# kick.net
KiCad netlist of a schematic drawn in EAGLE
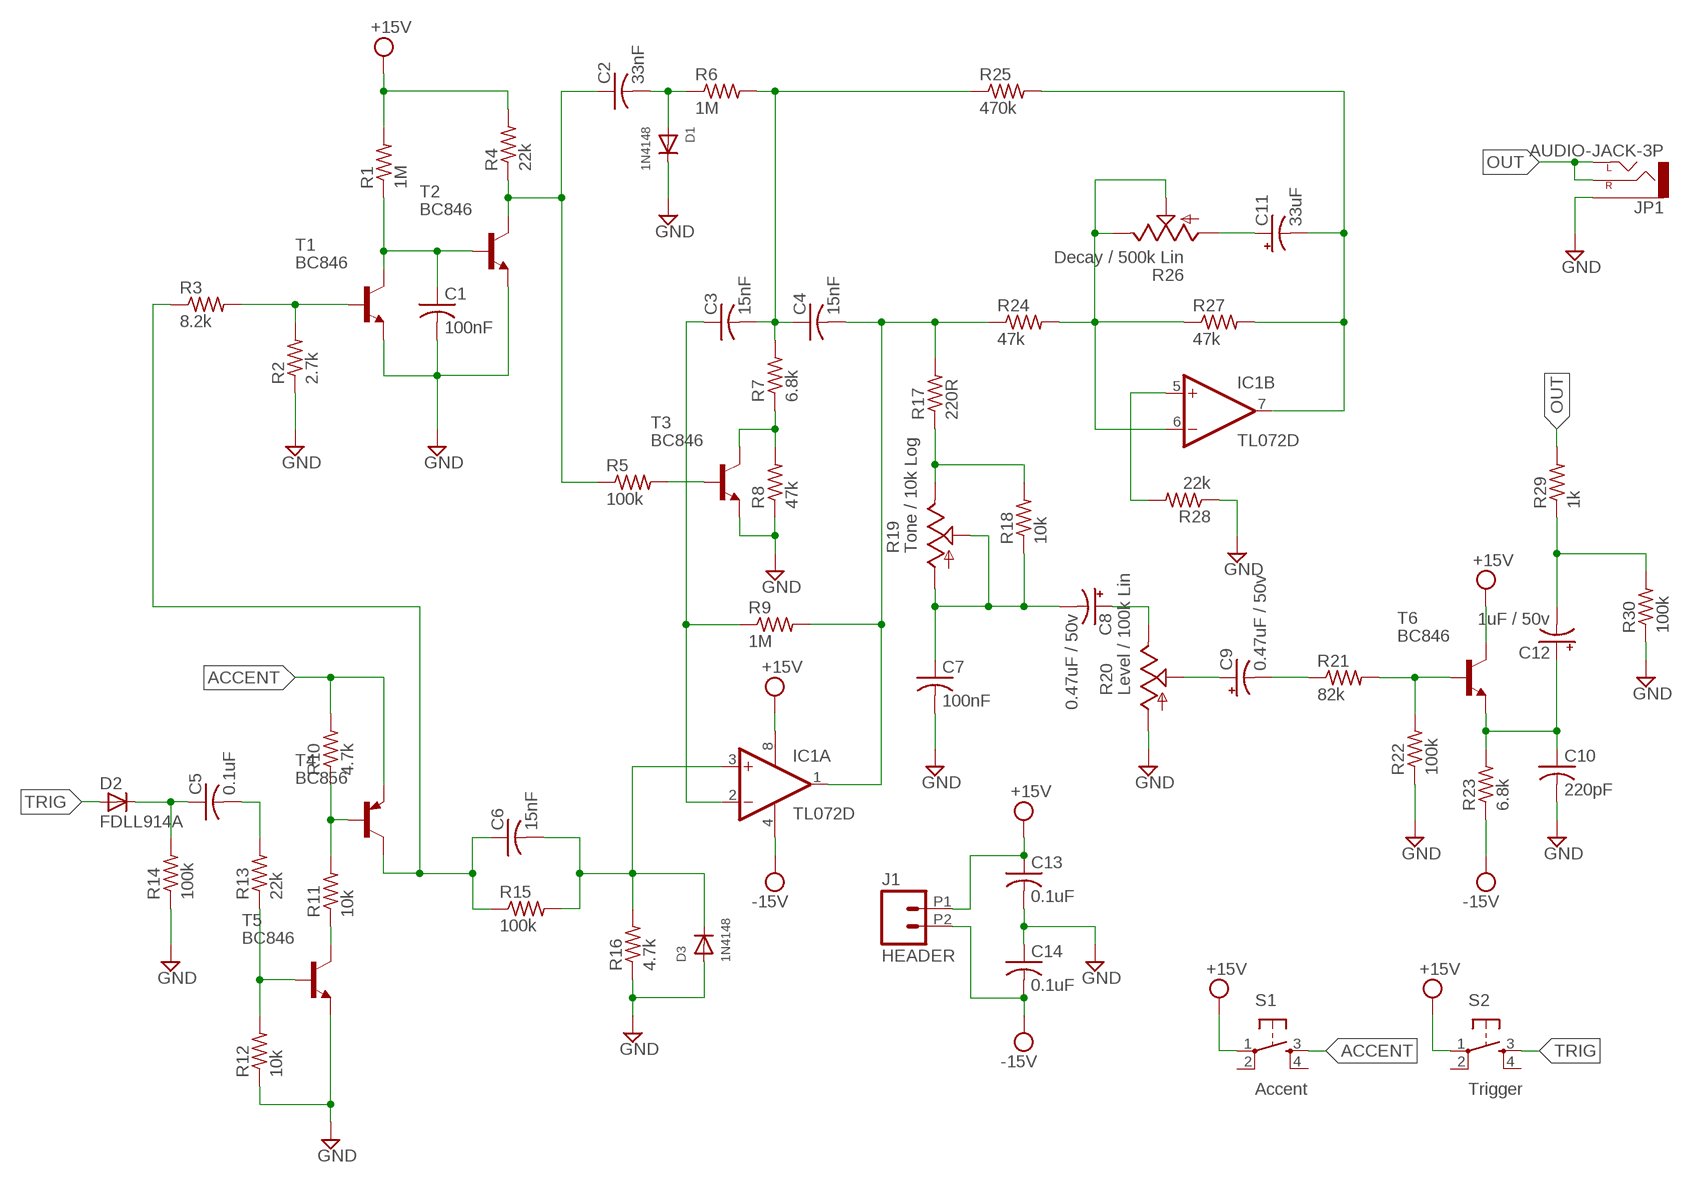
[diagram p0: schematic, sheet 1]

(export (version "E")
  (design (tool "Eeschema 10.0.6"))
  (components
    (comp (ref "C1")
      (value "100nF")
      (footprint "eagle-import:C0805")
      (fields (field (name "PARTNO") "C0805C104K5RACTU"))
      (libsource (lib "eagle-import") (part "C-USC0805"))
    )
    (comp (ref "C2")
      (value "33nF")
      (footprint "eagle-import:C0805")
      (fields (field (name "PARTNO") "CL21B333KBANNNC"))
      (libsource (lib "eagle-import") (part "C-USC0805"))
    )
    (comp (ref "C3")
      (value "15nF")
      (footprint "eagle-import:C0805")
      (fields (field (name "PARTNO") "CC0805KRX7R9BB153"))
      (libsource (lib "eagle-import") (part "C-USC0805"))
    )
    (comp (ref "C4")
      (value "15nF")
      (footprint "eagle-import:C0805")
      (fields (field (name "PARTNO") "CC0805KRX7R9BB153"))
      (libsource (lib "eagle-import") (part "C-USC0805"))
    )
    (comp (ref "C5")
      (value "0.1uF")
      (footprint "eagle-import:C0805")
      (fields (field (name "PARTNO") "C0805C104K5RACTU"))
      (libsource (lib "eagle-import") (part "C-USC0805"))
    )
    (comp (ref "C6")
      (value "15nF")
      (footprint "eagle-import:C0805")
      (fields (field (name "PARTNO") "CC0805KRX7R9BB153"))
      (libsource (lib "eagle-import") (part "C-USC0805"))
    )
    (comp (ref "C7")
      (value "100nF")
      (footprint "eagle-import:C0805")
      (fields (field (name "PARTNO") "C0805C104K5RACTU"))
      (libsource (lib "eagle-import") (part "C-USC0805"))
    )
    (comp (ref "C8")
      (value "0.47uF / 50v")
      (footprint "eagle-import:PANASONIC_VS_B-2")
      (fields (field (name "PARTNO") "EEE-1HAR47AR"))
      (libsource (lib "eagle-import") (part "CAP-POLPANASONIC_B-2"))
    )
    (comp (ref "C9")
      (value "0.47uF / 50v")
      (footprint "eagle-import:PANASONIC_VS_B-2")
      (fields (field (name "PARTNO") "EEE-1HAR47AR"))
      (libsource (lib "eagle-import") (part "CAP-POLPANASONIC_B-2"))
    )
    (comp (ref "C10")
      (value "220pF")
      (footprint "eagle-import:C0805")
      (fields (field (name "PARTNO") "CC0805KRX7R9BB221"))
      (libsource (lib "eagle-import") (part "C-USC0805"))
    )
    (comp (ref "C11")
      (value "33uF")
      (footprint "eagle-import:PANASONIC_VS_B-2")
      (fields (field (name "PARTNO") "EEE-1AA330WAR"))
      (libsource (lib "eagle-import") (part "CAP-POLPANASONIC_B-2"))
    )
    (comp (ref "C12")
      (value "1uF / 50v")
      (footprint "eagle-import:PANASONIC_VS_B-2")
      (fields (field (name "PARTNO") "EEE-1HA010SR"))
      (libsource (lib "eagle-import") (part "CAP-POLPANASONIC_B-2"))
    )
    (comp (ref "C13")
      (value "0.1uF")
      (footprint "eagle-import:C0805")
      (fields (field (name "PARTNO") "C0805C104K5RACTU"))
      (libsource (lib "eagle-import") (part "C-USC0805"))
    )
    (comp (ref "C14")
      (value "0.1uF")
      (footprint "eagle-import:C0805")
      (fields (field (name "PARTNO") "C0805C104K5RACTU"))
      (libsource (lib "eagle-import") (part "C-USC0805"))
    )
    (comp (ref "D1")
      (value "1N4148")
      (footprint "eagle-import:SOD-323F")
      (fields (field (name "PARTNO") "1N4148WS"))
      (libsource (lib "eagle-import") (part "DIODESOD-323F"))
    )
    (comp (ref "D2")
      (value "FDLL914A")
      (footprint "eagle-import:MELF-MLL34")
      (libsource (lib "eagle-import") (part "D-MLL-34"))
    )
    (comp (ref "D3")
      (value "1N4148")
      (footprint "eagle-import:SOD-323F")
      (fields (field (name "PARTNO") "1N4148WS"))
      (libsource (lib "eagle-import") (part "DIODESOD-323F"))
    )
    (comp (ref "IC1")
      (value "TL072D")
      (footprint "eagle-import:SO08")
      (fields (field (name "PARTNO") "TL072SG-13"))
      (libsource (lib "eagle-import") (part "TL072D"))
    )
    (comp (ref "J1")
      (value "HEADER")
      (footprint "eagle-import:1X02-5.08-SCREWTERM")
      (libsource (lib "eagle-import") (part "HEADER"))
    )
    (comp (ref "JP1")
      (value "AUDIO-JACK-3P")
      (footprint "eagle-import:CUI-352X-SMT")
      (fields (field (name "PARTNO") "SJ-3523-SMT-TR"))
      (libsource (lib "eagle-import") (part "AUDIO-JACK-3P"))
    )
    (comp (ref "R1")
      (value "1M")
      (footprint "eagle-import:R0805")
      (fields (field (name "PARTNO") "RMCF0805FT1M00"))
      (libsource (lib "eagle-import") (part "R-US_R0805"))
    )
    (comp (ref "R2")
      (value "2.7k")
      (footprint "eagle-import:R0805")
      (fields (field (name "PARTNO") "RMCF0805FT2K70"))
      (libsource (lib "eagle-import") (part "R-US_R0805"))
    )
    (comp (ref "R3")
      (value "8.2k")
      (footprint "eagle-import:R0805")
      (fields (field (name "PARTNO") "RMCF0805FT8K20"))
      (libsource (lib "eagle-import") (part "R-US_R0805"))
    )
    (comp (ref "R4")
      (value "22k")
      (footprint "eagle-import:R0805")
      (fields (field (name "PARTNO") "RMCF0805FT22K0"))
      (libsource (lib "eagle-import") (part "R-US_R0805"))
    )
    (comp (ref "R5")
      (value "100k")
      (footprint "eagle-import:R0805")
      (fields (field (name "PARTNO") "RMCF0805FT100K"))
      (libsource (lib "eagle-import") (part "R-US_R0805"))
    )
    (comp (ref "R6")
      (value "1M")
      (footprint "eagle-import:R0805")
      (fields (field (name "PARTNO") "RMCF0805FT1M00"))
      (libsource (lib "eagle-import") (part "R-US_R0805"))
    )
    (comp (ref "R7")
      (value "6.8k")
      (footprint "eagle-import:R0805")
      (fields (field (name "PARTNO") "MCR10ERTF6801"))
      (libsource (lib "eagle-import") (part "R-US_R0805"))
    )
    (comp (ref "R8")
      (value "47k")
      (footprint "eagle-import:R0805")
      (fields (field (name "PARTNO") "RMCF0805FT47K0"))
      (libsource (lib "eagle-import") (part "R-US_R0805"))
    )
    (comp (ref "R9")
      (value "1M")
      (footprint "eagle-import:R0805")
      (fields (field (name "PARTNO") "RMCF0805FT1M00"))
      (libsource (lib "eagle-import") (part "R-US_R0805"))
    )
    (comp (ref "R10")
      (value "4.7k")
      (footprint "eagle-import:R0805")
      (fields (field (name "PARTNO") "RMCF0805FT4K70"))
      (libsource (lib "eagle-import") (part "R-US_R0805"))
    )
    (comp (ref "R11")
      (value "10k")
      (footprint "eagle-import:R0805")
      (fields (field (name "PARTNO") "RMCF0805FT10K0"))
      (libsource (lib "eagle-import") (part "R-US_R0805"))
    )
    (comp (ref "R12")
      (value "10k")
      (footprint "eagle-import:R0805")
      (fields (field (name "PARTNO") "RMCF0805FT10K0"))
      (libsource (lib "eagle-import") (part "R-US_R0805"))
    )
    (comp (ref "R13")
      (value "22k")
      (footprint "eagle-import:R0805")
      (fields (field (name "PARTNO") "RMCF0805FT22K0"))
      (libsource (lib "eagle-import") (part "R-US_R0805"))
    )
    (comp (ref "R14")
      (value "100k")
      (footprint "eagle-import:R0805")
      (fields (field (name "PARTNO") "RMCF0805FT100K"))
      (libsource (lib "eagle-import") (part "R-US_R0805"))
    )
    (comp (ref "R15")
      (value "100k")
      (footprint "eagle-import:R0805")
      (fields (field (name "PARTNO") "RMCF0805FT100K"))
      (libsource (lib "eagle-import") (part "R-US_R0805"))
    )
    (comp (ref "R16")
      (value "4.7k")
      (footprint "eagle-import:R0805")
      (fields (field (name "PARTNO") "RMCF0805FT4K70"))
      (libsource (lib "eagle-import") (part "R-US_R0805"))
    )
    (comp (ref "R17")
      (value "220R")
      (footprint "eagle-import:R0805")
      (fields (field (name "PARTNO") "RMCF0805FT220R"))
      (libsource (lib "eagle-import") (part "R-US_R0805"))
    )
    (comp (ref "R18")
      (value "10k")
      (footprint "eagle-import:R0805")
      (fields (field (name "PARTNO") "RMCF0805FT10K0"))
      (libsource (lib "eagle-import") (part "R-US_R0805"))
    )
    (comp (ref "R19")
      (value "Tone / 10k Log")
      (footprint "eagle-import:POTENTIOMETER-PTV09")
      (fields (field (name "PARTNO") "PTV09A-4020F-A103"))
      (libsource (lib "eagle-import") (part "POTPTV09-H"))
    )
    (comp (ref "R20")
      (value "Level / 100k Lin")
      (footprint "eagle-import:POTENTIOMETER-CTS296")
      (fields (field (name "PARTNO") "296UD104B1N"))
      (libsource (lib "eagle-import") (part "POTCTS296"))
    )
    (comp (ref "R21")
      (value "82k")
      (footprint "eagle-import:R0805")
      (fields (field (name "PARTNO") "RMCF0805FT82K0"))
      (libsource (lib "eagle-import") (part "R-US_R0805"))
    )
    (comp (ref "R22")
      (value "100k")
      (footprint "eagle-import:R0805")
      (fields (field (name "PARTNO") "RMCF0805FT100K"))
      (libsource (lib "eagle-import") (part "R-US_R0805"))
    )
    (comp (ref "R23")
      (value "6.8k")
      (footprint "eagle-import:R0805")
      (fields (field (name "PARTNO") "MCR10ERTF6801"))
      (libsource (lib "eagle-import") (part "R-US_R0805"))
    )
    (comp (ref "R24")
      (value "47k")
      (footprint "eagle-import:R0805")
      (fields (field (name "PARTNO") "RMCF0805FT47K0"))
      (libsource (lib "eagle-import") (part "R-US_R0805"))
    )
    (comp (ref "R25")
      (value "470k")
      (footprint "eagle-import:R0805")
      (fields (field (name "PARTNO") "CRCW0805470KFKEA"))
      (libsource (lib "eagle-import") (part "R-US_R0805"))
    )
    (comp (ref "R26")
      (value "Decay / 500k Lin")
      (footprint "eagle-import:POTENTIOMETER-PTV09")
      (fields (field (name "PARTNO") "296UD504B1N"))
      (libsource (lib "eagle-import") (part "POTPTV09-H"))
    )
    (comp (ref "R27")
      (value "47k")
      (footprint "eagle-import:R0805")
      (fields (field (name "PARTNO") "RMCF0805FT47K0"))
      (libsource (lib "eagle-import") (part "R-US_R0805"))
    )
    (comp (ref "R28")
      (value "22k")
      (footprint "eagle-import:R0805")
      (fields (field (name "PARTNO") "RMCF0805FT22K0"))
      (libsource (lib "eagle-import") (part "R-US_R0805"))
    )
    (comp (ref "R29")
      (value "1k")
      (footprint "eagle-import:R0805")
      (fields (field (name "PARTNO") "RMCF0805FT1K00"))
      (libsource (lib "eagle-import") (part "R-US_R0805"))
    )
    (comp (ref "R30")
      (value "100k")
      (footprint "eagle-import:R0805")
      (fields (field (name "PARTNO") "RMCF0805FT100K"))
      (libsource (lib "eagle-import") (part "R-US_R0805"))
    )
    (comp (ref "S1")
      (value "Accent")
      (footprint "eagle-import:TACTILE-SWITCH-SMD")
      (fields (field (name "PARTNO") "PTS525SM10SMTR LFS"))
      (libsource (lib "eagle-import") (part "TAC_SWITCHSMD"))
    )
    (comp (ref "S2")
      (value "Trigger")
      (footprint "eagle-import:TACTILE-SWITCH-SMD")
      (fields (field (name "PARTNO") "PTS525SM10SMTR LFS"))
      (libsource (lib "eagle-import") (part "TAC_SWITCHSMD"))
    )
    (comp (ref "T1")
      (value "BC846")
      (footprint "eagle-import:SOT23")
      (fields (field (name "PARTNO") "BC846BMTF"))
      (libsource (lib "eagle-import") (part "BC846"))
    )
    (comp (ref "T2")
      (value "BC846")
      (footprint "eagle-import:SOT23")
      (fields (field (name "PARTNO") "BC846BMTF"))
      (libsource (lib "eagle-import") (part "BC846"))
    )
    (comp (ref "T3")
      (value "BC846")
      (footprint "eagle-import:SOT23")
      (fields (field (name "PARTNO") "BC846BMTF"))
      (libsource (lib "eagle-import") (part "BC846"))
    )
    (comp (ref "T4")
      (value "BC856")
      (footprint "eagle-import:SOT23-BEC")
      (fields (field (name "PARTNO") "BC856BMTF"))
      (libsource (lib "eagle-import") (part "-PNP-SOT23-BECBC856B"))
    )
    (comp (ref "T5")
      (value "BC846")
      (footprint "eagle-import:SOT23")
      (fields (field (name "PARTNO") "BC846BMTF"))
      (libsource (lib "eagle-import") (part "BC846"))
    )
    (comp (ref "T6")
      (value "BC846")
      (footprint "eagle-import:SOT23")
      (fields (field (name "PARTNO") "BC846BMTF"))
      (libsource (lib "eagle-import") (part "BC846"))
    )
  )
  (nets
    (net (code "1") (name "+15V") (class "Default")
      (node (ref "C13") (pin "1") (pinfunction "1_1") (pintype "passive"))
      (node (ref "IC1") (pin "8") (pinfunction "V+_8") (pintype "power_in"))
      (node (ref "J1") (pin "P1") (pinfunction "2_P1") (pintype "passive"))
      (node (ref "R1") (pin "2") (pinfunction "2_2") (pintype "passive"))
      (node (ref "R4") (pin "2") (pinfunction "2_2") (pintype "passive"))
      (node (ref "S1") (pin "1") (pinfunction "1_1") (pintype "passive"))
      (node (ref "S2") (pin "1") (pinfunction "1_1") (pintype "passive"))
      (node (ref "T6") (pin "3") (pinfunction "C_3") (pintype "passive"))
    )
    (net (code "2") (name "-15V") (class "Default")
      (node (ref "C14") (pin "2") (pinfunction "2_2") (pintype "passive"))
      (node (ref "IC1") (pin "4") (pinfunction "V-_4") (pintype "power_in"))
      (node (ref "J1") (pin "P2") (pinfunction "1_P2") (pintype "passive"))
      (node (ref "R23") (pin "1") (pinfunction "1_1") (pintype "passive"))
    )
    (net (code "3") (name "ACCENT") (class "Default")
      (node (ref "R10") (pin "2") (pinfunction "2_2") (pintype "passive"))
      (node (ref "S1") (pin "3") (pinfunction "3_3") (pintype "passive"))
      (node (ref "T4") (pin "E") (pinfunction "E_E") (pintype "passive"))
    )
    (net (code "4") (name "GND") (class "Default")
      (node (ref "C1") (pin "2") (pinfunction "2_2") (pintype "passive"))
      (node (ref "C10") (pin "2") (pinfunction "2_2") (pintype "passive"))
      (node (ref "C13") (pin "2") (pinfunction "2_2") (pintype "passive"))
      (node (ref "C14") (pin "1") (pinfunction "1_1") (pintype "passive"))
      (node (ref "C7") (pin "2") (pinfunction "2_2") (pintype "passive"))
      (node (ref "D1") (pin "C") (pinfunction "C_C") (pintype "passive"))
      (node (ref "D3") (pin "A") (pinfunction "A_A") (pintype "passive"))
      (node (ref "JP1") (pin "1") (pinfunction "SLEEVE_1") (pintype "bidirectional"))
      (node (ref "R12") (pin "1") (pinfunction "1_1") (pintype "passive"))
      (node (ref "R14") (pin "1") (pinfunction "1_1") (pintype "passive"))
      (node (ref "R16") (pin "1") (pinfunction "1_1") (pintype "passive"))
      (node (ref "R2") (pin "1") (pinfunction "1_1") (pintype "passive"))
      (node (ref "R20") (pin "P$1") (pinfunction "A_P$1") (pintype "passive"))
      (node (ref "R22") (pin "1") (pinfunction "1_1") (pintype "passive"))
      (node (ref "R28") (pin "1") (pinfunction "1_1") (pintype "passive"))
      (node (ref "R30") (pin "1") (pinfunction "1_1") (pintype "passive"))
      (node (ref "R8") (pin "1") (pinfunction "1_1") (pintype "passive"))
      (node (ref "T1") (pin "2") (pinfunction "E_2") (pintype "passive"))
      (node (ref "T2") (pin "2") (pinfunction "E_2") (pintype "passive"))
      (node (ref "T3") (pin "2") (pinfunction "E_2") (pintype "passive"))
      (node (ref "T5") (pin "2") (pinfunction "E_2") (pintype "passive"))
    )
    (net (code "5") (name "Net-(C2-Pad2)") (class "Default")
      (node (ref "C2") (pin "2") (pinfunction "2_2") (pintype "passive"))
      (node (ref "D1") (pin "A") (pinfunction "A_A") (pintype "passive"))
      (node (ref "R6") (pin "1") (pinfunction "1_1") (pintype "passive"))
    )
    (net (code "6") (name "Net-(C3-Pad2)") (class "Default")
      (node (ref "C3") (pin "2") (pinfunction "2_2") (pintype "passive"))
      (node (ref "C4") (pin "1") (pinfunction "1_1") (pintype "passive"))
      (node (ref "R25") (pin "1") (pinfunction "1_1") (pintype "passive"))
      (node (ref "R6") (pin "2") (pinfunction "2_2") (pintype "passive"))
      (node (ref "R7") (pin "2") (pinfunction "2_2") (pintype "passive"))
    )
    (net (code "7") (name "Net-(C5-Pad2)") (class "Default")
      (node (ref "C5") (pin "2") (pinfunction "2_2") (pintype "passive"))
      (node (ref "R13") (pin "2") (pinfunction "2_2") (pintype "passive"))
    )
    (net (code "8") (name "Net-(C6-Pad1)") (class "Default")
      (node (ref "C6") (pin "1") (pinfunction "1_1") (pintype "passive"))
      (node (ref "R15") (pin "1") (pinfunction "1_1") (pintype "passive"))
      (node (ref "R3") (pin "1") (pinfunction "1_1") (pintype "passive"))
      (node (ref "T4") (pin "C") (pinfunction "C_C") (pintype "passive"))
    )
    (net (code "9") (name "Net-(C9-Pad-)") (class "Default")
      (node (ref "C9") (pin "-") (pinfunction "-_-") (pintype "passive"))
      (node (ref "R21") (pin "1") (pinfunction "1_1") (pintype "passive"))
    )
    (net (code "10") (name "Net-(C12-Pad-)") (class "Default")
      (node (ref "C12") (pin "-") (pinfunction "-_-") (pintype "passive"))
      (node (ref "R29") (pin "1") (pinfunction "1_1") (pintype "passive"))
      (node (ref "R30") (pin "2") (pinfunction "2_2") (pintype "passive"))
    )
    (net (code "11") (name "Net-(D2-C)") (class "Default")
      (node (ref "C5") (pin "1") (pinfunction "1_1") (pintype "passive"))
      (node (ref "D2") (pin "1") (pinfunction "C_1") (pintype "passive"))
      (node (ref "R14") (pin "2") (pinfunction "2_2") (pintype "passive"))
    )
    (net (code "12") (name "Net-(IC1A-+IN)") (class "Default")
      (node (ref "C6") (pin "2") (pinfunction "2_2") (pintype "passive"))
      (node (ref "D3") (pin "C") (pinfunction "C_C") (pintype "passive"))
      (node (ref "IC1") (pin "3") (pinfunction "+IN_3") (pintype "input"))
      (node (ref "R15") (pin "2") (pinfunction "2_2") (pintype "passive"))
      (node (ref "R16") (pin "2") (pinfunction "2_2") (pintype "passive"))
    )
    (net (code "13") (name "Net-(IC1A--IN)") (class "Default")
      (node (ref "C3") (pin "1") (pinfunction "1_1") (pintype "passive"))
      (node (ref "IC1") (pin "2") (pinfunction "-IN_2") (pintype "input"))
      (node (ref "R9") (pin "1") (pinfunction "1_1") (pintype "passive"))
    )
    (net (code "14") (name "Net-(IC1A-OUT)") (class "Default")
      (node (ref "C4") (pin "2") (pinfunction "2_2") (pintype "passive"))
      (node (ref "IC1") (pin "1") (pinfunction "OUT_1") (pintype "output"))
      (node (ref "R17") (pin "2") (pinfunction "2_2") (pintype "passive"))
      (node (ref "R24") (pin "1") (pinfunction "1_1") (pintype "passive"))
      (node (ref "R9") (pin "2") (pinfunction "2_2") (pintype "passive"))
    )
    (net (code "15") (name "Net-(IC1B-+IN)") (class "Default")
      (node (ref "IC1") (pin "5") (pinfunction "+IN_5") (pintype "input"))
      (node (ref "R28") (pin "2") (pinfunction "2_2") (pintype "passive"))
    )
    (net (code "16") (name "Net-(IC1B--IN)") (class "Default")
      (node (ref "IC1") (pin "6") (pinfunction "-IN_6") (pintype "input"))
      (node (ref "R24") (pin "2") (pinfunction "2_2") (pintype "passive"))
      (node (ref "R26") (pin "P$2") (pinfunction "S_P$2") (pintype "passive"))
      (node (ref "R26") (pin "P$3") (pinfunction "E_P$3") (pintype "passive"))
      (node (ref "R27") (pin "1") (pinfunction "1_1") (pintype "passive"))
    )
    (net (code "17") (name "Net-(IC1B-OUT)") (class "Default")
      (node (ref "C11") (pin "-") (pinfunction "-_-") (pintype "passive"))
      (node (ref "IC1") (pin "7") (pinfunction "OUT_7") (pintype "output"))
      (node (ref "R25") (pin "2") (pinfunction "2_2") (pintype "passive"))
      (node (ref "R27") (pin "2") (pinfunction "2_2") (pintype "passive"))
    )
    (net (code "18") (name "Net-(R10-Pad1)") (class "Default")
      (node (ref "R10") (pin "1") (pinfunction "1_1") (pintype "passive"))
      (node (ref "R11") (pin "2") (pinfunction "2_2") (pintype "passive"))
      (node (ref "T4") (pin "B") (pinfunction "B_B") (pintype "passive"))
    )
    (net (code "19") (name "Net-(R19-A)") (class "Default")
      (node (ref "C7") (pin "1") (pinfunction "1_1") (pintype "passive"))
      (node (ref "C8") (pin "-") (pinfunction "-_-") (pintype "passive"))
      (node (ref "R18") (pin "1") (pinfunction "1_1") (pintype "passive"))
      (node (ref "R19") (pin "P$1") (pinfunction "A_P$1") (pintype "passive"))
      (node (ref "R19") (pin "P$2") (pinfunction "S_P$2") (pintype "passive"))
    )
    (net (code "20") (name "Net-(R19-E)") (class "Default")
      (node (ref "R17") (pin "1") (pinfunction "1_1") (pintype "passive"))
      (node (ref "R18") (pin "2") (pinfunction "2_2") (pintype "passive"))
      (node (ref "R19") (pin "P$3") (pinfunction "E_P$3") (pintype "passive"))
    )
    (net (code "21") (name "Net-(R20-E)") (class "Default")
      (node (ref "C8") (pin "+") (pinfunction "+_+") (pintype "passive"))
      (node (ref "R20") (pin "P$3") (pinfunction "E_P$3") (pintype "passive"))
    )
    (net (code "22") (name "Net-(R20-S)") (class "Default")
      (node (ref "C9") (pin "+") (pinfunction "+_+") (pintype "passive"))
      (node (ref "R20") (pin "P$2") (pinfunction "S_P$2") (pintype "passive"))
    )
    (net (code "23") (name "Net-(R26-A)") (class "Default")
      (node (ref "C11") (pin "+") (pinfunction "+_+") (pintype "passive"))
      (node (ref "R26") (pin "P$1") (pinfunction "A_P$1") (pintype "passive"))
    )
    (net (code "24") (name "Net-(T1-B)") (class "Default")
      (node (ref "R2") (pin "2") (pinfunction "2_2") (pintype "passive"))
      (node (ref "R3") (pin "2") (pinfunction "2_2") (pintype "passive"))
      (node (ref "T1") (pin "1") (pinfunction "B_1") (pintype "passive"))
    )
    (net (code "25") (name "Net-(T1-C)") (class "Default")
      (node (ref "C1") (pin "1") (pinfunction "1_1") (pintype "passive"))
      (node (ref "R1") (pin "1") (pinfunction "1_1") (pintype "passive"))
      (node (ref "T1") (pin "3") (pinfunction "C_3") (pintype "passive"))
      (node (ref "T2") (pin "1") (pinfunction "B_1") (pintype "passive"))
    )
    (net (code "26") (name "Net-(T2-C)") (class "Default")
      (node (ref "C2") (pin "1") (pinfunction "1_1") (pintype "passive"))
      (node (ref "R4") (pin "1") (pinfunction "1_1") (pintype "passive"))
      (node (ref "R5") (pin "1") (pinfunction "1_1") (pintype "passive"))
      (node (ref "T2") (pin "3") (pinfunction "C_3") (pintype "passive"))
    )
    (net (code "27") (name "Net-(T3-B)") (class "Default")
      (node (ref "R5") (pin "2") (pinfunction "2_2") (pintype "passive"))
      (node (ref "T3") (pin "1") (pinfunction "B_1") (pintype "passive"))
    )
    (net (code "28") (name "Net-(T3-C)") (class "Default")
      (node (ref "R7") (pin "1") (pinfunction "1_1") (pintype "passive"))
      (node (ref "R8") (pin "2") (pinfunction "2_2") (pintype "passive"))
      (node (ref "T3") (pin "3") (pinfunction "C_3") (pintype "passive"))
    )
    (net (code "29") (name "Net-(T5-B)") (class "Default")
      (node (ref "R12") (pin "2") (pinfunction "2_2") (pintype "passive"))
      (node (ref "R13") (pin "1") (pinfunction "1_1") (pintype "passive"))
      (node (ref "T5") (pin "1") (pinfunction "B_1") (pintype "passive"))
    )
    (net (code "30") (name "Net-(T5-C)") (class "Default")
      (node (ref "R11") (pin "1") (pinfunction "1_1") (pintype "passive"))
      (node (ref "T5") (pin "3") (pinfunction "C_3") (pintype "passive"))
    )
    (net (code "31") (name "Net-(T6-B)") (class "Default")
      (node (ref "R21") (pin "2") (pinfunction "2_2") (pintype "passive"))
      (node (ref "R22") (pin "2") (pinfunction "2_2") (pintype "passive"))
      (node (ref "T6") (pin "1") (pinfunction "B_1") (pintype "passive"))
    )
    (net (code "32") (name "Net-(T6-E)") (class "Default")
      (node (ref "C10") (pin "1") (pinfunction "1_1") (pintype "passive"))
      (node (ref "C12") (pin "+") (pinfunction "+_+") (pintype "passive"))
      (node (ref "R23") (pin "2") (pinfunction "2_2") (pintype "passive"))
      (node (ref "T6") (pin "2") (pinfunction "E_2") (pintype "passive"))
    )
    (net (code "33") (name "OUT") (class "Default")
      (node (ref "JP1") (pin "2") (pinfunction "LEFT_2") (pintype "bidirectional"))
      (node (ref "JP1") (pin "3") (pinfunction "RIGHT_3") (pintype "bidirectional"))
      (node (ref "R29") (pin "2") (pinfunction "2_2") (pintype "passive"))
    )
    (net (code "34") (name "TRIG") (class "Default")
      (node (ref "D2") (pin "2") (pinfunction "A_2") (pintype "passive"))
      (node (ref "S2") (pin "3") (pinfunction "3_3") (pintype "passive"))
    )
    (net (code "35") (name "unconnected-(S1-Pad2)") (class "Default")
      (node (ref "S1") (pin "2") (pinfunction "2_2") (pintype "passive"))
    )
    (net (code "36") (name "unconnected-(S1-Pad4)") (class "Default")
      (node (ref "S1") (pin "4") (pinfunction "4_4") (pintype "passive"))
    )
    (net (code "37") (name "unconnected-(S2-Pad2)") (class "Default")
      (node (ref "S2") (pin "2") (pinfunction "2_2") (pintype "passive"))
    )
    (net (code "38") (name "unconnected-(S2-Pad4)") (class "Default")
      (node (ref "S2") (pin "4") (pinfunction "4_4") (pintype "passive"))
    )
  )
)
